# motor_control.net
KiCad netlist of a schematic drawn in EAGLE
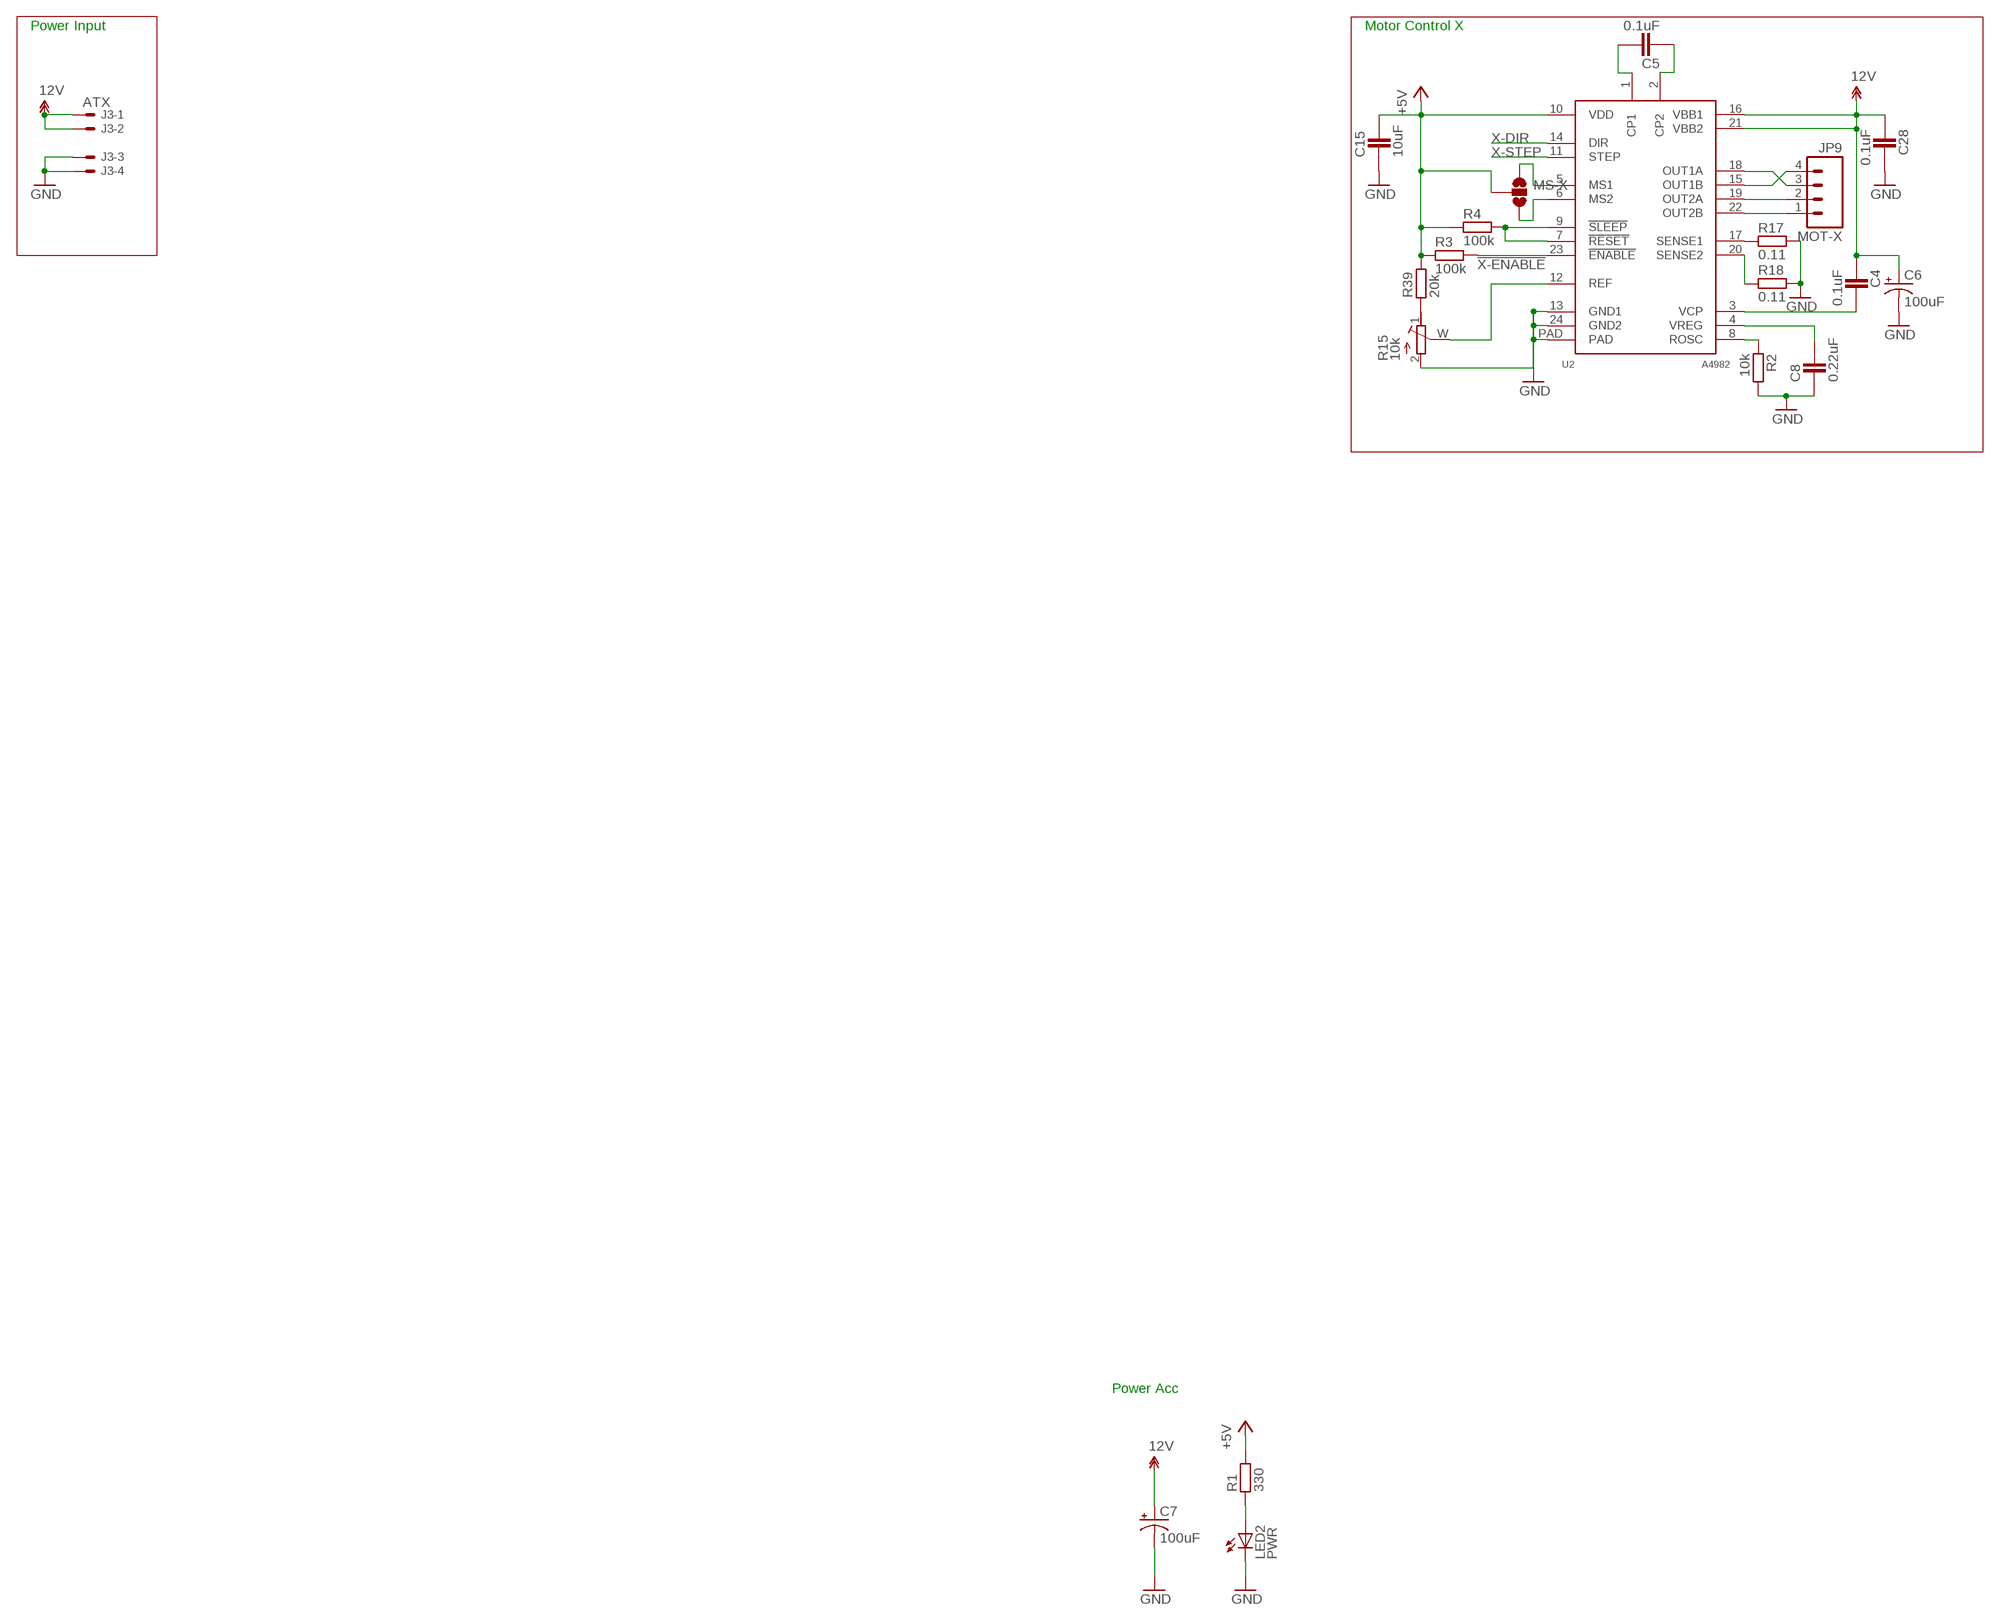
[diagram p0: schematic, sheet 1]

(export (version "E")
  (design (tool "Eeschema 10.0.6"))
  (components
    (comp (ref "C4")
      (value "0.1uF")
      (footprint "eagle-import:CAPC2012X145AN")
      (libsource (lib "eagle-import") (part "CAPACITOR_0805"))
    )
    (comp (ref "C5")
      (value "0.1uF")
      (footprint "eagle-import:CAPC2012X145AN")
      (libsource (lib "eagle-import") (part "CAPACITOR_0805"))
    )
    (comp (ref "C6")
      (value "100uF")
      (footprint "eagle-import:PANASONIC_D")
      (libsource (lib "eagle-import") (part "CPOL-USD"))
    )
    (comp (ref "C7")
      (value "100uF")
      (footprint "eagle-import:PANASONIC_D")
      (libsource (lib "eagle-import") (part "CPOL-USD"))
    )
    (comp (ref "C8")
      (value "0.22uF")
      (footprint "eagle-import:CAPC2012X145AN")
      (libsource (lib "eagle-import") (part "CAPACITOR_0805"))
    )
    (comp (ref "C15")
      (value "10uF")
      (footprint "eagle-import:CAPC2012X145AN")
      (libsource (lib "eagle-import") (part "CAPACITOR_0805"))
    )
    (comp (ref "C28")
      (value "0.1uF")
      (footprint "eagle-import:CAPC2012X145AN")
      (libsource (lib "eagle-import") (part "CAPACITOR_0805"))
    )
    (comp (ref "J3")
      (value "ATX")
      (footprint "eagle-import:5566-4")
      (libsource (lib "eagle-import") (part "5566-4"))
    )
    (comp (ref "JP9")
      (value "MOT-X")
      (footprint "eagle-import:MOLEX-1X4")
      (libsource (lib "eagle-import") (part "M04POLAR"))
    )
    (comp (ref "LED2")
      (value "PWR")
      (footprint "eagle-import:CHIP-LED0805")
      (libsource (lib "eagle-import") (part "LEDCHIP-LED0805"))
    )
    (comp (ref "MS-X")
      (value "SOLDERJUMPER_2WAYCONNECTED")
      (footprint "eagle-import:SJ_3_CONNECTED")
      (libsource (lib "eagle-import") (part "SOLDERJUMPER_2WAYCONNECTED"))
    )
    (comp (ref "R1")
      (value "330")
      (footprint "eagle-import:RESC2012X70N")
      (libsource (lib "eagle-import") (part "RESISTOR_0805"))
    )
    (comp (ref "R2")
      (value "10k")
      (footprint "eagle-import:RESC2012X70N")
      (libsource (lib "eagle-import") (part "RESISTOR_0805"))
    )
    (comp (ref "R3")
      (value "100k")
      (footprint "eagle-import:RESC2012X70N")
      (libsource (lib "eagle-import") (part "RESISTOR_0805"))
    )
    (comp (ref "R4")
      (value "100k")
      (footprint "eagle-import:RESC2012X70N")
      (libsource (lib "eagle-import") (part "RESISTOR_0805"))
    )
    (comp (ref "R15")
      (value "10k")
      (footprint "eagle-import:RTRIM-ST4ETB")
      (libsource (lib "eagle-import") (part "RTRIM-ST-4EA"))
    )
    (comp (ref "R17")
      (value "0.11")
      (footprint "eagle-import:RESC2012X70N")
      (libsource (lib "eagle-import") (part "RESISTOR_0805"))
    )
    (comp (ref "R18")
      (value "0.11")
      (footprint "eagle-import:RESC2012X70N")
      (libsource (lib "eagle-import") (part "RESISTOR_0805"))
    )
    (comp (ref "R39")
      (value "20k")
      (footprint "eagle-import:RESC2012X70N")
      (libsource (lib "eagle-import") (part "RESISTOR_0805"))
    )
    (comp (ref "U2")
      (value "A4982")
      (footprint "eagle-import:TSSOP-24")
      (libsource (lib "eagle-import") (part "A4982"))
    )
  )
  (nets
    (net (code "1") (name "+5V") (class "Default")
      (node (ref "C15") (pin "2") (pinfunction "2_2") (pintype "passive"))
      (node (ref "MS-X") (pin "2") (pinfunction "2_2") (pintype "passive"))
      (node (ref "R1") (pin "2") (pinfunction "2_2") (pintype "passive"))
      (node (ref "R3") (pin "1") (pinfunction "1_1") (pintype "passive"))
      (node (ref "R39") (pin "2") (pinfunction "2_2") (pintype "passive"))
      (node (ref "R4") (pin "1") (pinfunction "1_1") (pintype "passive"))
      (node (ref "U2") (pin "10") (pinfunction "VDD_10") (pintype "power_in"))
    )
    (net (code "2") (name "/X-DIR") (class "Default")
      (node (ref "U2") (pin "14") (pinfunction "DIR_14") (pintype "input"))
    )
    (net (code "3") (name "/X-STEP") (class "Default")
      (node (ref "U2") (pin "11") (pinfunction "STEP_11") (pintype "input"))
    )
    (net (code "4") (name "/~{X-ENABLE}") (class "Default")
      (node (ref "R3") (pin "2") (pinfunction "2_2") (pintype "passive"))
      (node (ref "U2") (pin "23") (pinfunction "~{ENABLE}_23") (pintype "input"))
    )
    (net (code "5") (name "12V") (class "Default")
      (node (ref "C28") (pin "1") (pinfunction "1_1") (pintype "passive"))
      (node (ref "C4") (pin "1") (pinfunction "1_1") (pintype "passive"))
      (node (ref "C6") (pin "+") (pinfunction "+_+") (pintype "passive"))
      (node (ref "C7") (pin "+") (pinfunction "+_+") (pintype "passive"))
      (node (ref "J3") (pin "1") (pinfunction "S_1") (pintype "passive"))
      (node (ref "J3") (pin "2") (pinfunction "S_2") (pintype "passive"))
      (node (ref "U2") (pin "16") (pinfunction "VBB1_16") (pintype "power_in"))
      (node (ref "U2") (pin "21") (pinfunction "VBB2_21") (pintype "power_in"))
    )
    (net (code "6") (name "GND") (class "Default")
      (node (ref "C15") (pin "1") (pinfunction "1_1") (pintype "passive"))
      (node (ref "C28") (pin "2") (pinfunction "2_2") (pintype "passive"))
      (node (ref "C6") (pin "-") (pinfunction "-_-") (pintype "passive"))
      (node (ref "C7") (pin "-") (pinfunction "-_-") (pintype "passive"))
      (node (ref "C8") (pin "1") (pinfunction "1_1") (pintype "passive"))
      (node (ref "J3") (pin "3") (pinfunction "S_3") (pintype "passive"))
      (node (ref "J3") (pin "4") (pinfunction "S_4") (pintype "passive"))
      (node (ref "LED2") (pin "C") (pinfunction "C_C") (pintype "passive"))
      (node (ref "R15") (pin "2") (pinfunction "E_2") (pintype "passive"))
      (node (ref "R17") (pin "2") (pinfunction "2_2") (pintype "passive"))
      (node (ref "R18") (pin "2") (pinfunction "2_2") (pintype "passive"))
      (node (ref "R2") (pin "2") (pinfunction "2_2") (pintype "passive"))
      (node (ref "U2") (pin "13") (pinfunction "GND1_13") (pintype "power_in"))
      (node (ref "U2") (pin "24") (pinfunction "GND2_24") (pintype "power_in"))
      (node (ref "U2") (pin "PAD") (pinfunction "PAD_PAD") (pintype "power_in"))
    )
    (net (code "7") (name "Net-(LED2-PadA)") (class "Default")
      (node (ref "LED2") (pin "A") (pinfunction "A_A") (pintype "passive"))
      (node (ref "R1") (pin "1") (pinfunction "1_1") (pintype "passive"))
    )
    (net (code "8") (name "Net-(R15-A)") (class "Default")
      (node (ref "R15") (pin "1") (pinfunction "A_1") (pintype "passive"))
      (node (ref "R39") (pin "1") (pinfunction "1_1") (pintype "passive"))
    )
    (net (code "9") (name "Net-(R15-S)") (class "Default")
      (node (ref "R15") (pin "W") (pinfunction "S_W") (pintype "passive"))
      (node (ref "U2") (pin "12") (pinfunction "REF_12") (pintype "input"))
    )
    (net (code "10") (name "Net-(U2-CP1)") (class "Default")
      (node (ref "C5") (pin "2") (pinfunction "2_2") (pintype "passive"))
      (node (ref "U2") (pin "1") (pinfunction "CP1_1") (pintype "passive"))
    )
    (net (code "11") (name "Net-(U2-CP2)") (class "Default")
      (node (ref "C5") (pin "1") (pinfunction "1_1") (pintype "passive"))
      (node (ref "U2") (pin "2") (pinfunction "CP2_2") (pintype "passive"))
    )
    (net (code "12") (name "Net-(U2-MS1)") (class "Default")
      (node (ref "MS-X") (pin "1") (pinfunction "1_1") (pintype "passive"))
      (node (ref "U2") (pin "5") (pinfunction "MS1_5") (pintype "input"))
    )
    (net (code "13") (name "Net-(U2-MS2)") (class "Default")
      (node (ref "MS-X") (pin "3") (pinfunction "3_3") (pintype "passive"))
      (node (ref "U2") (pin "6") (pinfunction "MS2_6") (pintype "input"))
    )
    (net (code "14") (name "Net-(U2-OUT1A)") (class "Default")
      (node (ref "JP9") (pin "3") (pinfunction "3_3") (pintype "passive"))
      (node (ref "U2") (pin "18") (pinfunction "OUT1A_18") (pintype "output"))
    )
    (net (code "15") (name "Net-(U2-OUT1B)") (class "Default")
      (node (ref "JP9") (pin "4") (pinfunction "4_4") (pintype "passive"))
      (node (ref "U2") (pin "15") (pinfunction "OUT1B_15") (pintype "output"))
    )
    (net (code "16") (name "Net-(U2-OUT2A)") (class "Default")
      (node (ref "JP9") (pin "2") (pinfunction "2_2") (pintype "passive"))
      (node (ref "U2") (pin "19") (pinfunction "OUT2A_19") (pintype "output"))
    )
    (net (code "17") (name "Net-(U2-OUT2B)") (class "Default")
      (node (ref "JP9") (pin "1") (pinfunction "1_1") (pintype "passive"))
      (node (ref "U2") (pin "22") (pinfunction "OUT2B_22") (pintype "output"))
    )
    (net (code "18") (name "Net-(U2-ROSC)") (class "Default")
      (node (ref "R2") (pin "1") (pinfunction "1_1") (pintype "passive"))
      (node (ref "U2") (pin "8") (pinfunction "ROSC_8") (pintype "passive"))
    )
    (net (code "19") (name "Net-(U2-SENSE1)") (class "Default")
      (node (ref "R17") (pin "1") (pinfunction "1_1") (pintype "passive"))
      (node (ref "U2") (pin "17") (pinfunction "SENSE1_17") (pintype "passive"))
    )
    (net (code "20") (name "Net-(U2-SENSE2)") (class "Default")
      (node (ref "R18") (pin "1") (pinfunction "1_1") (pintype "passive"))
      (node (ref "U2") (pin "20") (pinfunction "SENSE2_20") (pintype "passive"))
    )
    (net (code "21") (name "Net-(U2-VCP)") (class "Default")
      (node (ref "C4") (pin "2") (pinfunction "2_2") (pintype "passive"))
      (node (ref "U2") (pin "3") (pinfunction "VCP_3") (pintype "passive"))
    )
    (net (code "22") (name "Net-(U2-VREG)") (class "Default")
      (node (ref "C8") (pin "2") (pinfunction "2_2") (pintype "passive"))
      (node (ref "U2") (pin "4") (pinfunction "VREG_4") (pintype "passive"))
    )
    (net (code "23") (name "Net-(U2-~{RESET})") (class "Default")
      (node (ref "R4") (pin "2") (pinfunction "2_2") (pintype "passive"))
      (node (ref "U2") (pin "7") (pinfunction "~{RESET}_7") (pintype "input"))
      (node (ref "U2") (pin "9") (pinfunction "~{SLEEP}_9") (pintype "input"))
    )
  )
)
